# SmartMDC03.net
KiCad netlist of a schematic drawn in EAGLE
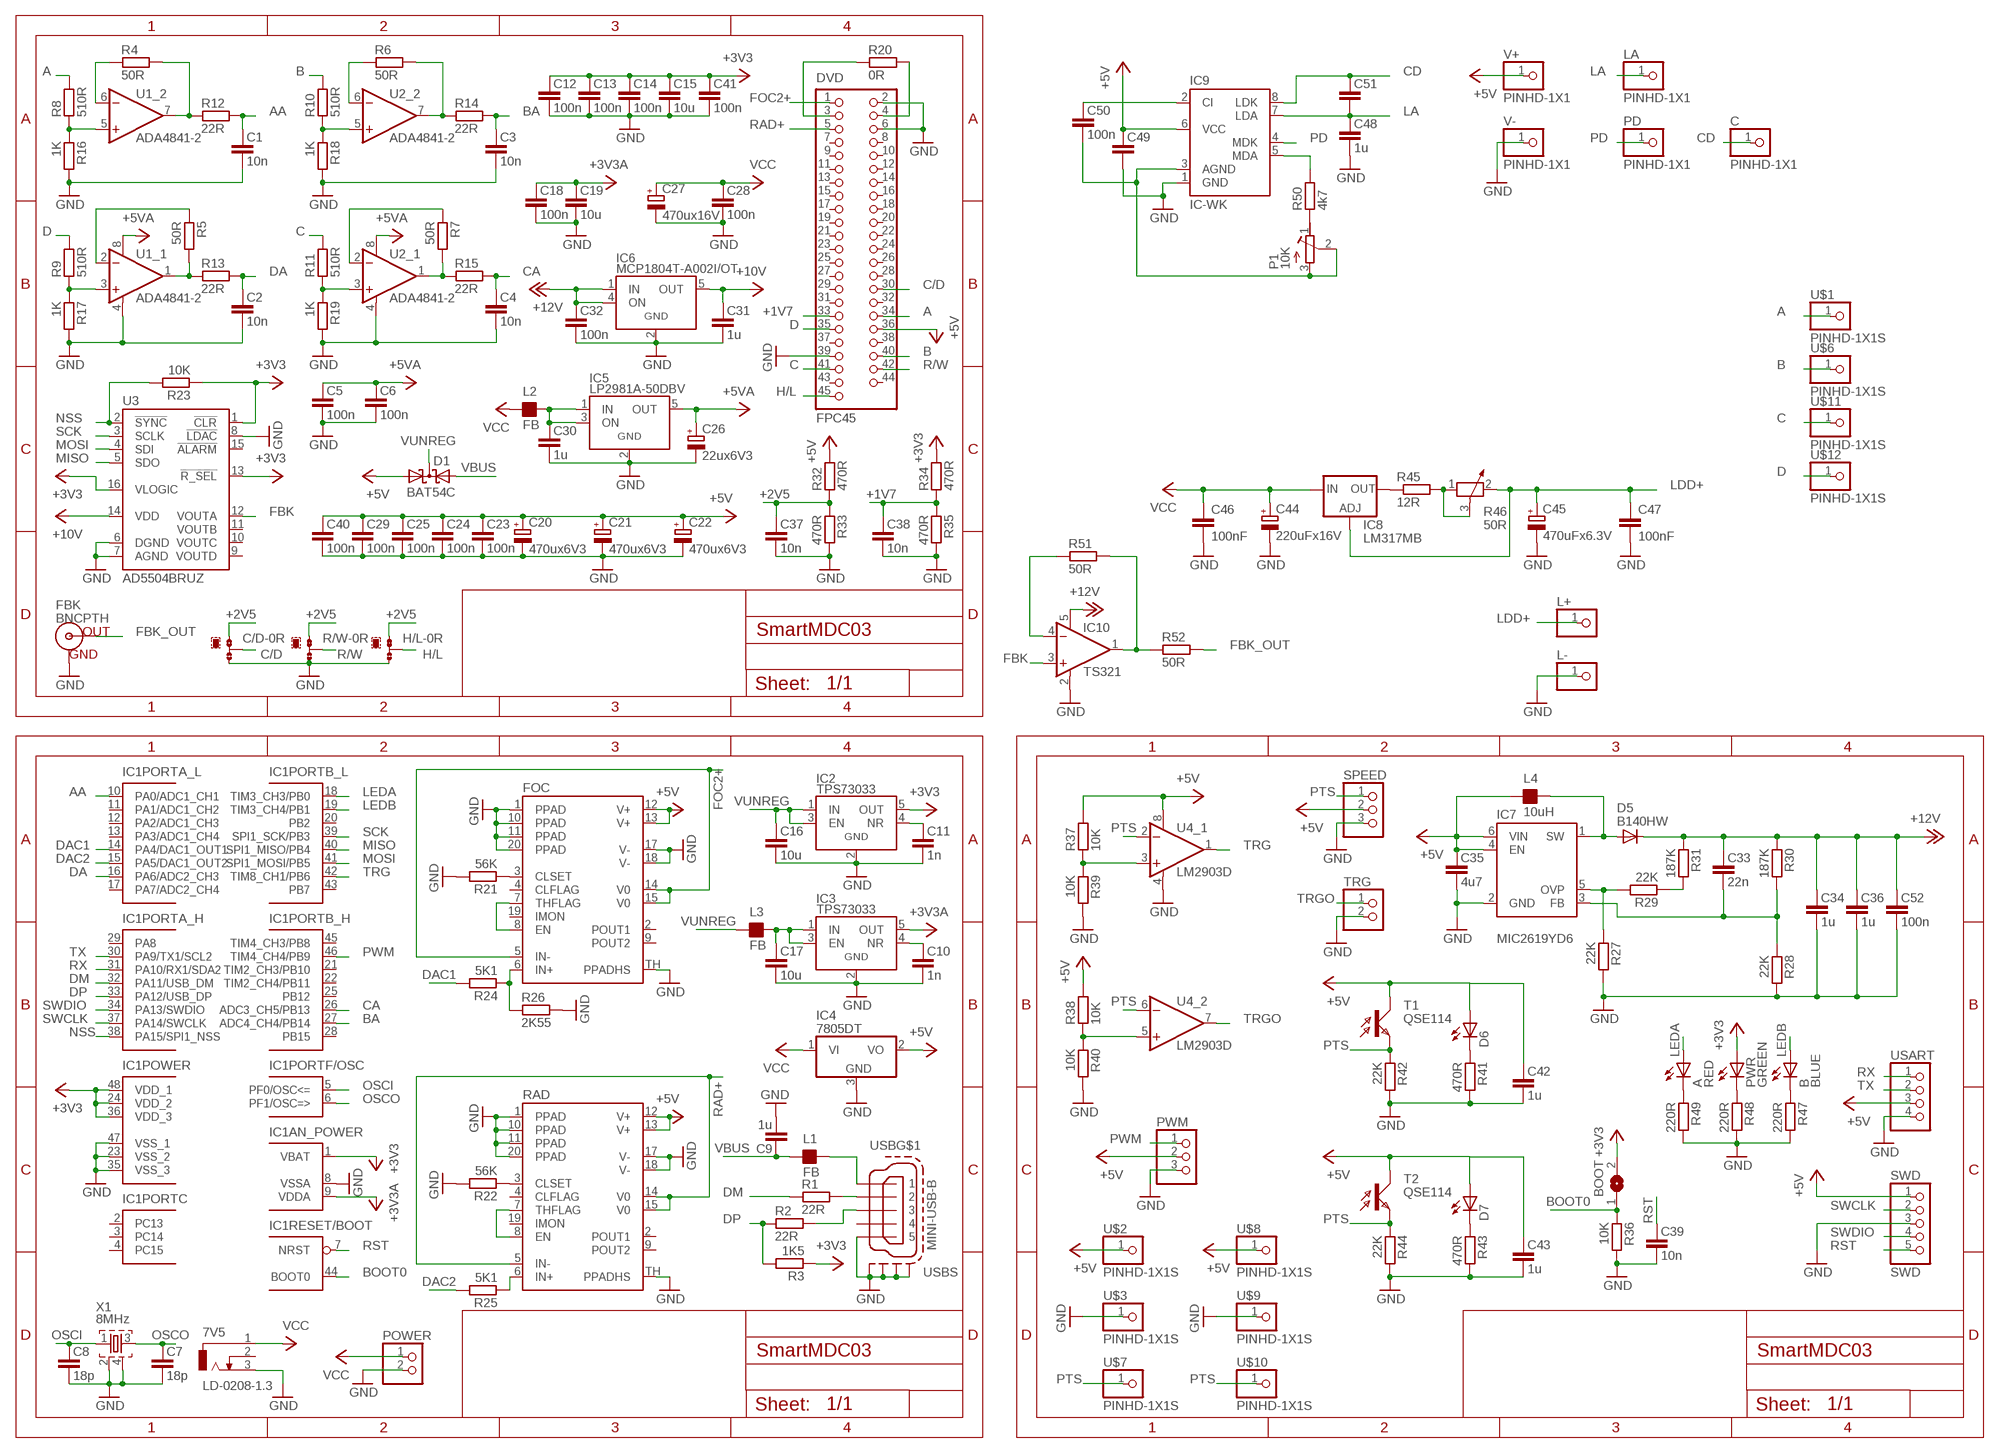
[diagram p0: schematic, sheet 1]

(export (version "E")
  (design (tool "Eeschema 10.0.6"))
  (components
    (comp (ref "7V5")
      (value "LD-0208-1.3")
      (footprint "eagle-import:LD-0208")
      (libsource (lib "eagle-import") (part "LD-0208-1.3"))
    )
    (comp (ref "A")
      (value "RED")
      (footprint "eagle-import:CHIPLED_0805")
      (libsource (lib "eagle-import") (part "LEDCHIPLED_0805"))
    )
    (comp (ref "B")
      (value "BLUE")
      (footprint "eagle-import:CHIPLED_0805")
      (libsource (lib "eagle-import") (part "LEDCHIPLED_0805"))
    )
    (comp (ref "BOOT")
      (value "SJ")
      (footprint "eagle-import:SJ")
      (libsource (lib "eagle-import") (part "SJ"))
    )
    (comp (ref "C")
      (value "PINHD-1X1")
      (footprint "eagle-import:1X01")
      (libsource (lib "eagle-import") (part "PINHD-1X1"))
    )
    (comp (ref "C/D")
      (value "0R-JUMPA")
      (footprint "eagle-import:A0R-JMP")
      (libsource (lib "eagle-import") (part "0R-JUMPA"))
    )
    (comp (ref "C1")
      (value "10n")
      (footprint "eagle-import:C0603G")
      (libsource (lib "eagle-import") (part "C_EU_C0603G"))
    )
    (comp (ref "C2")
      (value "10n")
      (footprint "eagle-import:C0603G")
      (libsource (lib "eagle-import") (part "C_EU_C0603G"))
    )
    (comp (ref "C3")
      (value "10n")
      (footprint "eagle-import:C0603G")
      (libsource (lib "eagle-import") (part "C_EU_C0603G"))
    )
    (comp (ref "C4")
      (value "10n")
      (footprint "eagle-import:C0603G")
      (libsource (lib "eagle-import") (part "C_EU_C0603G"))
    )
    (comp (ref "C5")
      (value "100n")
      (footprint "eagle-import:C0603G")
      (libsource (lib "eagle-import") (part "C_EU_C0603G"))
    )
    (comp (ref "C6")
      (value "100n")
      (footprint "eagle-import:C0603G")
      (libsource (lib "eagle-import") (part "C_EU_C0603G"))
    )
    (comp (ref "C7")
      (value "18p")
      (footprint "eagle-import:C0603G")
      (libsource (lib "eagle-import") (part "C_EU_C0603G"))
    )
    (comp (ref "C8")
      (value "18p")
      (footprint "eagle-import:C0603G")
      (libsource (lib "eagle-import") (part "C_EU_C0603G"))
    )
    (comp (ref "C9")
      (value "1u")
      (footprint "eagle-import:C0603G")
      (libsource (lib "eagle-import") (part "C_EU_C0603G"))
    )
    (comp (ref "C10")
      (value "1n")
      (footprint "eagle-import:C0603G")
      (libsource (lib "eagle-import") (part "C_EU_C0603G"))
    )
    (comp (ref "C11")
      (value "1n")
      (footprint "eagle-import:C0603G")
      (libsource (lib "eagle-import") (part "C_EU_C0603G"))
    )
    (comp (ref "C12")
      (value "100n")
      (footprint "eagle-import:C0603G")
      (libsource (lib "eagle-import") (part "C_EU_C0603G"))
    )
    (comp (ref "C13")
      (value "100n")
      (footprint "eagle-import:C0603G")
      (libsource (lib "eagle-import") (part "C_EU_C0603G"))
    )
    (comp (ref "C14")
      (value "100n")
      (footprint "eagle-import:C0603G")
      (libsource (lib "eagle-import") (part "C_EU_C0603G"))
    )
    (comp (ref "C15")
      (value "10u")
      (footprint "eagle-import:C0805G")
      (libsource (lib "eagle-import") (part "C_EU_C0805G"))
    )
    (comp (ref "C16")
      (value "10u")
      (footprint "eagle-import:C0805G")
      (libsource (lib "eagle-import") (part "C_EU_C0805G"))
    )
    (comp (ref "C17")
      (value "10u")
      (footprint "eagle-import:C0805G")
      (libsource (lib "eagle-import") (part "C_EU_C0805G"))
    )
    (comp (ref "C18")
      (value "100n")
      (footprint "eagle-import:C0603G")
      (libsource (lib "eagle-import") (part "C_EU_C0603G"))
    )
    (comp (ref "C19")
      (value "10u")
      (footprint "eagle-import:C0805G")
      (libsource (lib "eagle-import") (part "C_EU_C0805G"))
    )
    (comp (ref "C20")
      (value "470ux6V3")
      (footprint "eagle-import:SMC_D")
      (libsource (lib "eagle-import") (part "CPOL-EUSMCD"))
    )
    (comp (ref "C21")
      (value "470ux6V3")
      (footprint "eagle-import:SMC_D")
      (libsource (lib "eagle-import") (part "CPOL-EUSMCD"))
    )
    (comp (ref "C22")
      (value "470ux6V3")
      (footprint "eagle-import:SMC_D")
      (libsource (lib "eagle-import") (part "CPOL-EUSMCD"))
    )
    (comp (ref "C23")
      (value "100n")
      (footprint "eagle-import:C0603G")
      (libsource (lib "eagle-import") (part "C_EU_C0603G"))
    )
    (comp (ref "C24")
      (value "100n")
      (footprint "eagle-import:C0603G")
      (libsource (lib "eagle-import") (part "C_EU_C0603G"))
    )
    (comp (ref "C25")
      (value "100n")
      (footprint "eagle-import:C0603G")
      (libsource (lib "eagle-import") (part "C_EU_C0603G"))
    )
    (comp (ref "C26")
      (value "22ux6V3")
      (footprint "eagle-import:SMC_A")
      (libsource (lib "eagle-import") (part "CPOL-EUSMCA"))
    )
    (comp (ref "C27")
      (value "470ux16V")
      (footprint "eagle-import:E2,5-7")
      (libsource (lib "eagle-import") (part "CPOL-EUE2.5-7"))
    )
    (comp (ref "C28")
      (value "100n")
      (footprint "eagle-import:C0603G")
      (libsource (lib "eagle-import") (part "C_EU_C0603G"))
    )
    (comp (ref "C29")
      (value "100n")
      (footprint "eagle-import:C0603G")
      (libsource (lib "eagle-import") (part "C_EU_C0603G"))
    )
    (comp (ref "C30")
      (value "1u")
      (footprint "eagle-import:C0603G")
      (libsource (lib "eagle-import") (part "C_EU_C0603G"))
    )
    (comp (ref "C31")
      (value "1u")
      (footprint "eagle-import:C0603G")
      (libsource (lib "eagle-import") (part "C_EU_C0603G"))
    )
    (comp (ref "C32")
      (value "100n")
      (footprint "eagle-import:C0603G")
      (libsource (lib "eagle-import") (part "C_EU_C0603G"))
    )
    (comp (ref "C33")
      (value "22n")
      (footprint "eagle-import:C0603")
      (libsource (lib "eagle-import") (part "C_EU_C0603"))
    )
    (comp (ref "C34")
      (value "1u")
      (footprint "eagle-import:C0603G")
      (libsource (lib "eagle-import") (part "C_EU_C0603G"))
    )
    (comp (ref "C35")
      (value "4u7")
      (footprint "eagle-import:C0603G")
      (libsource (lib "eagle-import") (part "C_EU_C0603G"))
    )
    (comp (ref "C36")
      (value "1u")
      (footprint "eagle-import:C0603G")
      (libsource (lib "eagle-import") (part "C_EU_C0603G"))
    )
    (comp (ref "C37")
      (value "10n")
      (footprint "eagle-import:C0603G")
      (libsource (lib "eagle-import") (part "C_EU_C0603G"))
    )
    (comp (ref "C38")
      (value "10n")
      (footprint "eagle-import:C0603G")
      (libsource (lib "eagle-import") (part "C_EU_C0603G"))
    )
    (comp (ref "C39")
      (value "10n")
      (footprint "eagle-import:C0603G")
      (libsource (lib "eagle-import") (part "C_EU_C0603G"))
    )
    (comp (ref "C40")
      (value "100n")
      (footprint "eagle-import:C0603G")
      (libsource (lib "eagle-import") (part "C_EU_C0603G"))
    )
    (comp (ref "C41")
      (value "100n")
      (footprint "eagle-import:C0603G")
      (libsource (lib "eagle-import") (part "C_EU_C0603G"))
    )
    (comp (ref "C42")
      (value "1u")
      (footprint "eagle-import:C0603G")
      (libsource (lib "eagle-import") (part "C_EU_C0603G"))
    )
    (comp (ref "C43")
      (value "1u")
      (footprint "eagle-import:C0603G")
      (libsource (lib "eagle-import") (part "C_EU_C0603G"))
    )
    (comp (ref "C44")
      (value "220uFx16V")
      (footprint "eagle-import:E3,5-8")
      (libsource (lib "eagle-import") (part "CPOL-EUE3.5-8"))
    )
    (comp (ref "C45")
      (value "470uFx6.3V")
      (footprint "eagle-import:E3,5-8")
      (libsource (lib "eagle-import") (part "CPOL-EUE3.5-8"))
    )
    (comp (ref "C46")
      (value "100nF")
      (footprint "eagle-import:C050-024X044")
      (libsource (lib "eagle-import") (part "C-EU050-024X044"))
    )
    (comp (ref "C47")
      (value "100nF")
      (footprint "eagle-import:C050-024X044")
      (libsource (lib "eagle-import") (part "C-EU050-024X044"))
    )
    (comp (ref "C48")
      (value "1u")
      (footprint "eagle-import:C0805")
      (libsource (lib "eagle-import") (part "C_EU_C0805"))
    )
    (comp (ref "C49")
      (value "C_EU_C0805")
      (footprint "eagle-import:C0805")
      (libsource (lib "eagle-import") (part "C_EU_C0805"))
    )
    (comp (ref "C50")
      (value "100n")
      (footprint "eagle-import:C0805")
      (libsource (lib "eagle-import") (part "C_EU_C0805"))
    )
    (comp (ref "C51")
      (value "C_EU_C0805")
      (footprint "eagle-import:C0805")
      (libsource (lib "eagle-import") (part "C_EU_C0805"))
    )
    (comp (ref "C52")
      (value "100n")
      (footprint "eagle-import:C0603G")
      (libsource (lib "eagle-import") (part "C_EU_C0603G"))
    )
    (comp (ref "D1")
      (value "BAT54C")
      (footprint "eagle-import:SOT23")
      (libsource (lib "eagle-import") (part "BAT54C"))
    )
    (comp (ref "D5")
      (value "B140HW")
      (footprint "eagle-import:SOD123")
      (libsource (lib "eagle-import") (part "B140HW"))
    )
    (comp (ref "D6")
      (value "OP240")
      (footprint "eagle-import:OP240")
      (libsource (lib "eagle-import") (part "OP240"))
    )
    (comp (ref "D7")
      (value "OP240")
      (footprint "eagle-import:OP240")
      (libsource (lib "eagle-import") (part "OP240"))
    )
    (comp (ref "DVD")
      (value "FPC45")
      (footprint "eagle-import:FPC45")
      (libsource (lib "eagle-import") (part "CON-FPC45"))
    )
    (comp (ref "FBK")
      (value "BNCPTH")
      (footprint "eagle-import:BNC")
      (libsource (lib "eagle-import") (part "BNCPTH"))
    )
    (comp (ref "FOC")
      (value "OPA569")
      (footprint "eagle-import:SO-20")
      (libsource (lib "eagle-import") (part "OPA569"))
    )
    (comp (ref "H/L")
      (value "0R-JUMPA")
      (footprint "eagle-import:A0R-JMP")
      (libsource (lib "eagle-import") (part "0R-JUMPA"))
    )
    (comp (ref "IC1")
      (value "STM32F303CXT6")
      (footprint "eagle-import:LQFP48")
      (libsource (lib "eagle-import") (part "STM32F303CXT6"))
    )
    (comp (ref "IC2")
      (value "TPS73033")
      (footprint "eagle-import:SOT23-5")
      (libsource (lib "eagle-import") (part "TPS769XX"))
    )
    (comp (ref "IC3")
      (value "TPS73033")
      (footprint "eagle-import:SOT23-5")
      (libsource (lib "eagle-import") (part "TPS769XX"))
    )
    (comp (ref "IC4")
      (value "7805DT")
      (footprint "eagle-import:TO252")
      (libsource (lib "eagle-import") (part "78DT05"))
    )
    (comp (ref "IC5")
      (value "LP2981A-50DBV")
      (footprint "eagle-import:SOT23-5")
      (libsource (lib "eagle-import") (part "LP2981A-50DBV"))
    )
    (comp (ref "IC6")
      (value "MCP1804T-A002I/OT")
      (footprint "eagle-import:SOT23-5")
      (libsource (lib "eagle-import") (part "MCP1804T-A002I/OT"))
    )
    (comp (ref "IC7")
      (value "MIC2619YD6")
      (footprint "eagle-import:SOT23-6")
      (libsource (lib "eagle-import") (part "MIC2619YD6"))
    )
    (comp (ref "IC8")
      (value "LM317MB")
      (footprint "eagle-import:TO220L1")
      (libsource (lib "eagle-import") (part "LM317?MB"))
    )
    (comp (ref "IC9")
      (value "IC-WK")
      (footprint "eagle-import:SOIC-8")
      (libsource (lib "eagle-import") (part "IC-WK"))
    )
    (comp (ref "IC10")
      (value "TS321")
      (footprint "eagle-import:SOT23-5")
      (libsource (lib "eagle-import") (part "TS321"))
    )
    (comp (ref "L+")
      (value "PINHD-1X1")
      (footprint "eagle-import:1X01")
      (libsource (lib "eagle-import") (part "pinhead_PINHD-1X1"))
    )
    (comp (ref "L-")
      (value "PINHD-1X1")
      (footprint "eagle-import:1X01")
      (libsource (lib "eagle-import") (part "pinhead_PINHD-1X1"))
    )
    (comp (ref "L1")
      (value "FB")
      (footprint "eagle-import:L0603")
      (libsource (lib "eagle-import") (part "FB_0603"))
    )
    (comp (ref "L2")
      (value "FB")
      (footprint "eagle-import:L0603")
      (libsource (lib "eagle-import") (part "FB_0603"))
    )
    (comp (ref "L3")
      (value "FB")
      (footprint "eagle-import:L0603")
      (libsource (lib "eagle-import") (part "FB_0603"))
    )
    (comp (ref "L4")
      (value "10uH")
      (footprint "eagle-import:L1210")
      (libsource (lib "eagle-import") (part "FB_1210"))
    )
    (comp (ref "LA")
      (value "PINHD-1X1")
      (footprint "eagle-import:1X01")
      (libsource (lib "eagle-import") (part "PINHD-1X1"))
    )
    (comp (ref "P1")
      (value "10K")
      (footprint "eagle-import:RTRIM3165W")
      (libsource (lib "eagle-import") (part "R-TRIMM3165W"))
    )
    (comp (ref "PD")
      (value "PINHD-1X1")
      (footprint "eagle-import:1X01")
      (libsource (lib "eagle-import") (part "PINHD-1X1"))
    )
    (comp (ref "POWER")
      (value "PINHD-1X2")
      (footprint "eagle-import:1X02")
      (libsource (lib "eagle-import") (part "PINHD-1X2"))
    )
    (comp (ref "PWM")
      (value "PINHD-1X3")
      (footprint "eagle-import:1X03")
      (libsource (lib "eagle-import") (part "PINHD-1X3"))
    )
    (comp (ref "PWR")
      (value "GREEN")
      (footprint "eagle-import:CHIPLED_0805")
      (libsource (lib "eagle-import") (part "LEDCHIPLED_0805"))
    )
    (comp (ref "R/W")
      (value "0R-JUMPA")
      (footprint "eagle-import:A0R-JMP")
      (libsource (lib "eagle-import") (part "0R-JUMPA"))
    )
    (comp (ref "R1")
      (value "22R")
      (footprint "eagle-import:R0603")
      (libsource (lib "eagle-import") (part "R_EU_R0603"))
    )
    (comp (ref "R2")
      (value "22R")
      (footprint "eagle-import:R0603")
      (libsource (lib "eagle-import") (part "R_EU_R0603"))
    )
    (comp (ref "R3")
      (value "1K5")
      (footprint "eagle-import:R0603")
      (libsource (lib "eagle-import") (part "R_EU_R0603"))
    )
    (comp (ref "R4")
      (value "50R")
      (footprint "eagle-import:R0603")
      (libsource (lib "eagle-import") (part "R_EU_R0603"))
    )
    (comp (ref "R5")
      (value "50R")
      (footprint "eagle-import:R0603")
      (libsource (lib "eagle-import") (part "R_EU_R0603"))
    )
    (comp (ref "R6")
      (value "50R")
      (footprint "eagle-import:R0603")
      (libsource (lib "eagle-import") (part "R_EU_R0603"))
    )
    (comp (ref "R7")
      (value "50R")
      (footprint "eagle-import:R0603")
      (libsource (lib "eagle-import") (part "R_EU_R0603"))
    )
    (comp (ref "R8")
      (value "510R")
      (footprint "eagle-import:R0603")
      (libsource (lib "eagle-import") (part "R_EU_R0603"))
    )
    (comp (ref "R9")
      (value "510R")
      (footprint "eagle-import:R0603")
      (libsource (lib "eagle-import") (part "R_EU_R0603"))
    )
    (comp (ref "R10")
      (value "510R")
      (footprint "eagle-import:R0603")
      (libsource (lib "eagle-import") (part "R_EU_R0603"))
    )
    (comp (ref "R11")
      (value "510R")
      (footprint "eagle-import:R0603")
      (libsource (lib "eagle-import") (part "R_EU_R0603"))
    )
    (comp (ref "R12")
      (value "22R")
      (footprint "eagle-import:R0603")
      (libsource (lib "eagle-import") (part "R_EU_R0603"))
    )
    (comp (ref "R13")
      (value "22R")
      (footprint "eagle-import:R0603")
      (libsource (lib "eagle-import") (part "R_EU_R0603"))
    )
    (comp (ref "R14")
      (value "22R")
      (footprint "eagle-import:R0603")
      (libsource (lib "eagle-import") (part "R_EU_R0603"))
    )
    (comp (ref "R15")
      (value "22R")
      (footprint "eagle-import:R0603")
      (libsource (lib "eagle-import") (part "R_EU_R0603"))
    )
    (comp (ref "R16")
      (value "1K")
      (footprint "eagle-import:R0603G")
      (libsource (lib "eagle-import") (part "R_EU_R0603G"))
    )
    (comp (ref "R17")
      (value "1K")
      (footprint "eagle-import:R0603G")
      (libsource (lib "eagle-import") (part "R_EU_R0603G"))
    )
    (comp (ref "R18")
      (value "1K")
      (footprint "eagle-import:R0603G")
      (libsource (lib "eagle-import") (part "R_EU_R0603G"))
    )
    (comp (ref "R19")
      (value "1K")
      (footprint "eagle-import:R0603G")
      (libsource (lib "eagle-import") (part "R_EU_R0603G"))
    )
    (comp (ref "R20")
      (value "0R")
      (footprint "eagle-import:R0603")
      (libsource (lib "eagle-import") (part "R_EU_R0603"))
    )
    (comp (ref "R21")
      (value "56K")
      (footprint "eagle-import:R0603G")
      (libsource (lib "eagle-import") (part "R_EU_R0603G"))
    )
    (comp (ref "R22")
      (value "56K")
      (footprint "eagle-import:R0603G")
      (libsource (lib "eagle-import") (part "R_EU_R0603G"))
    )
    (comp (ref "R23")
      (value "10K")
      (footprint "eagle-import:R0603")
      (libsource (lib "eagle-import") (part "R_EU_R0603"))
    )
    (comp (ref "R24")
      (value "5K1")
      (footprint "eagle-import:R0603")
      (libsource (lib "eagle-import") (part "R_EU_R0603"))
    )
    (comp (ref "R25")
      (value "5K1")
      (footprint "eagle-import:R0603")
      (libsource (lib "eagle-import") (part "R_EU_R0603"))
    )
    (comp (ref "R26")
      (value "2K55")
      (footprint "eagle-import:R0603G")
      (libsource (lib "eagle-import") (part "R_EU_R0603G"))
    )
    (comp (ref "R27")
      (value "22K")
      (footprint "eagle-import:R0603G")
      (libsource (lib "eagle-import") (part "R_EU_R0603G"))
    )
    (comp (ref "R28")
      (value "22K")
      (footprint "eagle-import:R0603G")
      (libsource (lib "eagle-import") (part "R_EU_R0603G"))
    )
    (comp (ref "R29")
      (value "22K")
      (footprint "eagle-import:R0603")
      (libsource (lib "eagle-import") (part "R_EU_R0603"))
    )
    (comp (ref "R30")
      (value "187K")
      (footprint "eagle-import:R0603")
      (libsource (lib "eagle-import") (part "R_EU_R0603"))
    )
    (comp (ref "R31")
      (value "187K")
      (footprint "eagle-import:R0603")
      (libsource (lib "eagle-import") (part "R_EU_R0603"))
    )
    (comp (ref "R32")
      (value "470R")
      (footprint "eagle-import:R0603")
      (libsource (lib "eagle-import") (part "R_EU_R0603"))
    )
    (comp (ref "R33")
      (value "470R")
      (footprint "eagle-import:R0603G")
      (libsource (lib "eagle-import") (part "R_EU_R0603G"))
    )
    (comp (ref "R34")
      (value "470R")
      (footprint "eagle-import:R0603")
      (libsource (lib "eagle-import") (part "R_EU_R0603"))
    )
    (comp (ref "R35")
      (value "470R")
      (footprint "eagle-import:R0603G")
      (libsource (lib "eagle-import") (part "R_EU_R0603G"))
    )
    (comp (ref "R36")
      (value "10K")
      (footprint "eagle-import:R0603G")
      (libsource (lib "eagle-import") (part "R_EU_R0603G"))
    )
    (comp (ref "R37")
      (value "10K")
      (footprint "eagle-import:R0603")
      (libsource (lib "eagle-import") (part "R_EU_R0603"))
    )
    (comp (ref "R38")
      (value "10K")
      (footprint "eagle-import:R0603")
      (libsource (lib "eagle-import") (part "R_EU_R0603"))
    )
    (comp (ref "R39")
      (value "10K")
      (footprint "eagle-import:R0603G")
      (libsource (lib "eagle-import") (part "R_EU_R0603G"))
    )
    (comp (ref "R40")
      (value "10K")
      (footprint "eagle-import:R0603G")
      (libsource (lib "eagle-import") (part "R_EU_R0603G"))
    )
    (comp (ref "R41")
      (value "470R")
      (footprint "eagle-import:R0603G")
      (libsource (lib "eagle-import") (part "R_EU_R0603G"))
    )
    (comp (ref "R42")
      (value "22K")
      (footprint "eagle-import:R0603G")
      (libsource (lib "eagle-import") (part "R_EU_R0603G"))
    )
    (comp (ref "R43")
      (value "470R")
      (footprint "eagle-import:R0603G")
      (libsource (lib "eagle-import") (part "R_EU_R0603G"))
    )
    (comp (ref "R44")
      (value "22K")
      (footprint "eagle-import:R0603G")
      (libsource (lib "eagle-import") (part "R_EU_R0603G"))
    )
    (comp (ref "R45")
      (value "12R")
      (footprint "eagle-import:0207_7")
      (libsource (lib "eagle-import") (part "R-EU_0207/7"))
    )
    (comp (ref "R46")
      (value "50R")
      (footprint "eagle-import:PT-SPIN")
      (libsource (lib "eagle-import") (part "POTENTIOMETER_PT_SPIN"))
    )
    (comp (ref "R47")
      (value "220R")
      (footprint "eagle-import:R0603G")
      (libsource (lib "eagle-import") (part "R_EU_R0603G"))
    )
    (comp (ref "R48")
      (value "220R")
      (footprint "eagle-import:R0603G")
      (libsource (lib "eagle-import") (part "R_EU_R0603G"))
    )
    (comp (ref "R49")
      (value "220R")
      (footprint "eagle-import:R0603G")
      (libsource (lib "eagle-import") (part "R_EU_R0603G"))
    )
    (comp (ref "R50")
      (value "4k7")
      (footprint "eagle-import:R0805")
      (libsource (lib "eagle-import") (part "R_EU_R0805"))
    )
    (comp (ref "R51")
      (value "50R")
      (footprint "eagle-import:R0603")
      (libsource (lib "eagle-import") (part "R_EU_R0603"))
    )
    (comp (ref "R52")
      (value "50R")
      (footprint "eagle-import:R0603")
      (libsource (lib "eagle-import") (part "R_EU_R0603"))
    )
    (comp (ref "RAD")
      (value "OPA569")
      (footprint "eagle-import:SO-20")
      (libsource (lib "eagle-import") (part "OPA569"))
    )
    (comp (ref "SPEED")
      (value "PINHD-1X3")
      (footprint "eagle-import:1X03")
      (libsource (lib "eagle-import") (part "PINHD-1X3"))
    )
    (comp (ref "SWD")
      (value "SWD")
      (footprint "eagle-import:1X05")
      (libsource (lib "eagle-import") (part "PINHD-1X5"))
    )
    (comp (ref "T1")
      (value "QSE114")
      (footprint "eagle-import:QSE114")
      (libsource (lib "eagle-import") (part "QSE114"))
    )
    (comp (ref "T2")
      (value "QSE114")
      (footprint "eagle-import:QSE114")
      (libsource (lib "eagle-import") (part "QSE114"))
    )
    (comp (ref "TRG")
      (value "PINHD-1X2")
      (footprint "eagle-import:1X02")
      (libsource (lib "eagle-import") (part "PINHD-1X2"))
    )
    (comp (ref "U$1")
      (value "PINHD-1X1S")
      (footprint "eagle-import:1X01S")
      (libsource (lib "eagle-import") (part "PINHD-1X1S"))
    )
    (comp (ref "U$2")
      (value "PINHD-1X1S")
      (footprint "eagle-import:1X01S")
      (libsource (lib "eagle-import") (part "PINHD-1X1S"))
    )
    (comp (ref "U$3")
      (value "PINHD-1X1S")
      (footprint "eagle-import:1X01S")
      (libsource (lib "eagle-import") (part "PINHD-1X1S"))
    )
    (comp (ref "U$6")
      (value "PINHD-1X1S")
      (footprint "eagle-import:1X01S")
      (libsource (lib "eagle-import") (part "PINHD-1X1S"))
    )
    (comp (ref "U$7")
      (value "PINHD-1X1S")
      (footprint "eagle-import:1X01S")
      (libsource (lib "eagle-import") (part "PINHD-1X1S"))
    )
    (comp (ref "U$8")
      (value "PINHD-1X1S")
      (footprint "eagle-import:1X01S")
      (libsource (lib "eagle-import") (part "PINHD-1X1S"))
    )
    (comp (ref "U$9")
      (value "PINHD-1X1S")
      (footprint "eagle-import:1X01S")
      (libsource (lib "eagle-import") (part "PINHD-1X1S"))
    )
    (comp (ref "U$10")
      (value "PINHD-1X1S")
      (footprint "eagle-import:1X01S")
      (libsource (lib "eagle-import") (part "PINHD-1X1S"))
    )
    (comp (ref "U$11")
      (value "PINHD-1X1S")
      (footprint "eagle-import:1X01S")
      (libsource (lib "eagle-import") (part "PINHD-1X1S"))
    )
    (comp (ref "U$12")
      (value "PINHD-1X1S")
      (footprint "eagle-import:1X01S")
      (libsource (lib "eagle-import") (part "PINHD-1X1S"))
    )
    (comp (ref "U1")
      (value "ADA4841-2")
      (footprint "eagle-import:SOIC-8")
      (libsource (lib "eagle-import") (part "ADA4841-2"))
    )
    (comp (ref "U2")
      (value "ADA4841-2")
      (footprint "eagle-import:SOIC-8")
      (libsource (lib "eagle-import") (part "ADA4841-2"))
    )
    (comp (ref "U3")
      (value "AD5504BRUZ")
      (footprint "eagle-import:TSSOP16")
      (libsource (lib "eagle-import") (part "AD5504BRUZ"))
    )
    (comp (ref "U4")
      (value "LM2903D")
      (footprint "eagle-import:SOIC-8")
      (libsource (lib "eagle-import") (part "LM2903D"))
    )
    (comp (ref "USART")
      (value "PINHD-1X4")
      (footprint "eagle-import:1X04")
      (libsource (lib "eagle-import") (part "PINHD-1X4"))
    )
    (comp (ref "USB")
      (value "MINI-USB-B")
      (footprint "eagle-import:32005-201")
      (libsource (lib "eagle-import") (part "MINI-USB-SCHIELD-32005-201"))
    )
    (comp (ref "V+")
      (value "PINHD-1X1")
      (footprint "eagle-import:1X01")
      (libsource (lib "eagle-import") (part "PINHD-1X1"))
    )
    (comp (ref "V-")
      (value "PINHD-1X1")
      (footprint "eagle-import:1X01")
      (libsource (lib "eagle-import") (part "PINHD-1X1"))
    )
    (comp (ref "X1")
      (value "8MHz")
      (footprint "eagle-import:ABMM2")
      (libsource (lib "eagle-import") (part "ABMM2"))
    )
  )
  (nets
    (net (code "1") (name "+3V3") (class "Default")
      (node (ref "BOOT") (pin "2") (pinfunction "2_2") (pintype "passive"))
      (node (ref "C12") (pin "1") (pinfunction "1_1") (pintype "passive"))
      (node (ref "C13") (pin "1") (pinfunction "1_1") (pintype "passive"))
      (node (ref "C14") (pin "1") (pinfunction "1_1") (pintype "passive"))
      (node (ref "C15") (pin "1") (pinfunction "1_1") (pintype "passive"))
      (node (ref "C41") (pin "1") (pinfunction "1_1") (pintype "passive"))
      (node (ref "IC1") (pin "1") (pinfunction "VBAT_1") (pintype "power_in"))
      (node (ref "IC1") (pin "24") (pinfunction "VDD_2_24") (pintype "power_in"))
      (node (ref "IC1") (pin "36") (pinfunction "VDD_3_36") (pintype "power_in"))
      (node (ref "IC1") (pin "48") (pinfunction "VDD_1_48") (pintype "power_in"))
      (node (ref "IC2") (pin "5") (pinfunction "OUT_5") (pintype "power_in"))
      (node (ref "PWR") (pin "A") (pinfunction "A_A") (pintype "passive"))
      (node (ref "R23") (pin "1") (pinfunction "1_1") (pintype "passive"))
      (node (ref "R3") (pin "1") (pinfunction "1_1") (pintype "passive"))
      (node (ref "R34") (pin "2") (pinfunction "2_2") (pintype "passive"))
      (node (ref "U3") (pin "1") (pinfunction "~{CLR}_1") (pintype "input"))
      (node (ref "U3") (pin "13") (pinfunction "~{R_SEL}_13") (pintype "input"))
      (node (ref "U3") (pin "16") (pinfunction "VLOGIC_16") (pintype "power_in"))
    )
    (net (code "2") (name "+3V3A") (class "Default")
      (node (ref "C18") (pin "1") (pinfunction "1_1") (pintype "passive"))
      (node (ref "C19") (pin "1") (pinfunction "1_1") (pintype "passive"))
      (node (ref "IC1") (pin "9") (pinfunction "VDDA_9") (pintype "power_in"))
      (node (ref "IC3") (pin "5") (pinfunction "OUT_5") (pintype "power_in"))
    )
    (net (code "3") (name "+5V") (class "Default")
      (node (ref "C20") (pin "+") (pinfunction "+_+") (pintype "passive"))
      (node (ref "C21") (pin "+") (pinfunction "+_+") (pintype "passive"))
      (node (ref "C22") (pin "+") (pinfunction "+_+") (pintype "passive"))
      (node (ref "C23") (pin "1") (pinfunction "1_1") (pintype "passive"))
      (node (ref "C24") (pin "1") (pinfunction "1_1") (pintype "passive"))
      (node (ref "C25") (pin "1") (pinfunction "1_1") (pintype "passive"))
      (node (ref "C29") (pin "1") (pinfunction "1_1") (pintype "passive"))
      (node (ref "C35") (pin "1") (pinfunction "1_1") (pintype "passive"))
      (node (ref "C40") (pin "1") (pinfunction "1_1") (pintype "passive"))
      (node (ref "C42") (pin "1") (pinfunction "1_1") (pintype "passive"))
      (node (ref "C43") (pin "1") (pinfunction "1_1") (pintype "passive"))
      (node (ref "C49") (pin "1") (pinfunction "1_1") (pintype "passive"))
      (node (ref "D1") (pin "1") (pinfunction "A1_1") (pintype "passive"))
      (node (ref "D6") (pin "A") (pinfunction "A_A") (pintype "passive"))
      (node (ref "D7") (pin "A") (pinfunction "A_A") (pintype "passive"))
      (node (ref "DVD") (pin "36") (pinfunction "36_36") (pintype "passive"))
      (node (ref "FOC") (pin "12") (pinfunction "V+_12") (pintype "bidirectional"))
      (node (ref "FOC") (pin "13") (pinfunction "V+_13") (pintype "bidirectional"))
      (node (ref "IC4") (pin "2") (pinfunction "VO_2") (pintype "passive"))
      (node (ref "IC7") (pin "4") (pinfunction "EN_4") (pintype "input"))
      (node (ref "IC7") (pin "6") (pinfunction "VIN_6") (pintype "power_in"))
      (node (ref "IC9") (pin "6") (pinfunction "VCC_6") (pintype "bidirectional"))
      (node (ref "L4") (pin "1") (pinfunction "1_1") (pintype "passive"))
      (node (ref "PWM") (pin "2") (pinfunction "2_2") (pintype "passive"))
      (node (ref "R32") (pin "2") (pinfunction "2_2") (pintype "passive"))
      (node (ref "R37") (pin "2") (pinfunction "2_2") (pintype "passive"))
      (node (ref "R38") (pin "2") (pinfunction "2_2") (pintype "passive"))
      (node (ref "RAD") (pin "12") (pinfunction "V+_12") (pintype "bidirectional"))
      (node (ref "RAD") (pin "13") (pinfunction "V+_13") (pintype "bidirectional"))
      (node (ref "SPEED") (pin "2") (pinfunction "2_2") (pintype "passive"))
      (node (ref "SWD") (pin "1") (pinfunction "1_1") (pintype "passive"))
      (node (ref "T1") (pin "C") (pinfunction "C_C") (pintype "passive"))
      (node (ref "T2") (pin "C") (pinfunction "C_C") (pintype "passive"))
      (node (ref "U$2") (pin "1") (pinfunction "1_1") (pintype "passive"))
      (node (ref "U$8") (pin "1") (pinfunction "1_1") (pintype "passive"))
      (node (ref "U4") (pin "8") (pinfunction "V+_8") (pintype "power_in"))
      (node (ref "USART") (pin "3") (pinfunction "3_3") (pintype "passive"))
      (node (ref "V+") (pin "1") (pinfunction "1_1") (pintype "passive"))
    )
    (net (code "4") (name "+5VA") (class "Default")
      (node (ref "C26") (pin "+") (pinfunction "+_+") (pintype "passive"))
      (node (ref "C5") (pin "1") (pinfunction "1_1") (pintype "passive"))
      (node (ref "C6") (pin "1") (pinfunction "1_1") (pintype "passive"))
      (node (ref "IC5") (pin "5") (pinfunction "OUT_5") (pintype "power_in"))
      (node (ref "U1") (pin "8") (pinfunction "V+_8") (pintype "power_in"))
      (node (ref "U2") (pin "8") (pinfunction "V+_8") (pintype "power_in"))
    )
    (net (code "5") (name "+10V") (class "Default")
      (node (ref "C31") (pin "1") (pinfunction "1_1") (pintype "passive"))
      (node (ref "IC6") (pin "5") (pinfunction "OUT_5") (pintype "power_in"))
      (node (ref "U3") (pin "14") (pinfunction "VDD_14") (pintype "power_in"))
    )
    (net (code "6") (name "+12V") (class "Default")
      (node (ref "C32") (pin "1") (pinfunction "1_1") (pintype "passive"))
      (node (ref "C33") (pin "1") (pinfunction "1_1") (pintype "passive"))
      (node (ref "C34") (pin "1") (pinfunction "1_1") (pintype "passive"))
      (node (ref "C36") (pin "1") (pinfunction "1_1") (pintype "passive"))
      (node (ref "C52") (pin "1") (pinfunction "1_1") (pintype "passive"))
      (node (ref "D5") (pin "C") (pinfunction "C_C") (pintype "passive"))
      (node (ref "IC10") (pin "5") (pinfunction "V+_5") (pintype "power_in"))
      (node (ref "IC6") (pin "1") (pinfunction "IN_1") (pintype "power_in"))
      (node (ref "IC6") (pin "4") (pinfunction "ON_4") (pintype "passive"))
      (node (ref "R30") (pin "1") (pinfunction "1_1") (pintype "passive"))
      (node (ref "R31") (pin "1") (pinfunction "1_1") (pintype "passive"))
    )
    (net (code "7") (name "/+1V7") (class "Default")
      (node (ref "C38") (pin "1") (pinfunction "1_1") (pintype "passive"))
      (node (ref "DVD") (pin "33") (pinfunction "33_33") (pintype "passive"))
      (node (ref "R34") (pin "1") (pinfunction "1_1") (pintype "passive"))
      (node (ref "R35") (pin "1") (pinfunction "1_1") (pintype "passive"))
    )
    (net (code "8") (name "/+2V5") (class "Default")
      (node (ref "C/D") (pin "1") (pinfunction "1_1") (pintype "passive"))
      (node (ref "C37") (pin "1") (pinfunction "1_1") (pintype "passive"))
      (node (ref "H/L") (pin "1") (pinfunction "1_1") (pintype "passive"))
      (node (ref "R/W") (pin "1") (pinfunction "1_1") (pintype "passive"))
      (node (ref "R32") (pin "1") (pinfunction "1_1") (pintype "passive"))
      (node (ref "R33") (pin "1") (pinfunction "1_1") (pintype "passive"))
    )
    (net (code "9") (name "/A") (class "Default")
      (node (ref "DVD") (pin "34") (pinfunction "34_34") (pintype "passive"))
      (node (ref "R8") (pin "2") (pinfunction "2_2") (pintype "passive"))
      (node (ref "U$1") (pin "1") (pinfunction "1_1") (pintype "passive"))
    )
    (net (code "10") (name "/AA") (class "Default")
      (node (ref "C1") (pin "1") (pinfunction "1_1") (pintype "passive"))
      (node (ref "IC1") (pin "10") (pinfunction "PA0/ADC1_CH1_10") (pintype "bidirectional"))
      (node (ref "R12") (pin "2") (pinfunction "2_2") (pintype "passive"))
    )
    (net (code "11") (name "/B") (class "Default")
      (node (ref "DVD") (pin "40") (pinfunction "40_40") (pintype "passive"))
      (node (ref "R10") (pin "2") (pinfunction "2_2") (pintype "passive"))
      (node (ref "U$6") (pin "1") (pinfunction "1_1") (pintype "passive"))
    )
    (net (code "12") (name "/BA") (class "Default")
      (node (ref "C3") (pin "1") (pinfunction "1_1") (pintype "passive"))
      (node (ref "IC1") (pin "27") (pinfunction "ADC4_CH4/PB14_27") (pintype "bidirectional"))
      (node (ref "R14") (pin "2") (pinfunction "2_2") (pintype "passive"))
    )
    (net (code "13") (name "/BOOT0") (class "Default")
      (node (ref "BOOT") (pin "1") (pinfunction "1_1") (pintype "passive"))
      (node (ref "IC1") (pin "44") (pinfunction "BOOT0_44") (pintype "input"))
      (node (ref "R36") (pin "1") (pinfunction "1_1") (pintype "passive"))
    )
    (net (code "14") (name "/C") (class "Default")
      (node (ref "DVD") (pin "41") (pinfunction "41_41") (pintype "passive"))
      (node (ref "R11") (pin "2") (pinfunction "2_2") (pintype "passive"))
      (node (ref "U$11") (pin "1") (pinfunction "1_1") (pintype "passive"))
    )
    (net (code "15") (name "/CA") (class "Default")
      (node (ref "C4") (pin "1") (pinfunction "1_1") (pintype "passive"))
      (node (ref "IC1") (pin "26") (pinfunction "ADC3_CH5/PB13_26") (pintype "bidirectional"))
      (node (ref "R15") (pin "2") (pinfunction "2_2") (pintype "passive"))
    )
    (net (code "16") (name "/CD") (class "Default")
      (node (ref "C") (pin "1") (pinfunction "1_1") (pintype "passive"))
      (node (ref "C51") (pin "1") (pinfunction "1_1") (pintype "passive"))
      (node (ref "IC9") (pin "8") (pinfunction "LDK_8") (pintype "bidirectional"))
    )
    (net (code "17") (name "/C{slash}D") (class "Default")
      (node (ref "C/D") (pin "2") (pinfunction "2_2") (pintype "passive"))
      (node (ref "DVD") (pin "30") (pinfunction "30_30") (pintype "passive"))
    )
    (net (code "18") (name "/D") (class "Default")
      (node (ref "DVD") (pin "35") (pinfunction "35_35") (pintype "passive"))
      (node (ref "R9") (pin "2") (pinfunction "2_2") (pintype "passive"))
      (node (ref "U$12") (pin "1") (pinfunction "1_1") (pintype "passive"))
    )
    (net (code "19") (name "/DA") (class "Default")
      (node (ref "C2") (pin "1") (pinfunction "1_1") (pintype "passive"))
      (node (ref "IC1") (pin "16") (pinfunction "PA6/ADC2_CH3_16") (pintype "bidirectional"))
      (node (ref "R13") (pin "2") (pinfunction "2_2") (pintype "passive"))
    )
    (net (code "20") (name "/DAC1") (class "Default")
      (node (ref "IC1") (pin "14") (pinfunction "PA4/DAC1_OUT1_14") (pintype "bidirectional"))
      (node (ref "R24") (pin "2") (pinfunction "2_2") (pintype "passive"))
    )
    (net (code "21") (name "/DAC2") (class "Default")
      (node (ref "IC1") (pin "15") (pinfunction "PA5/DAC1_OUT2_15") (pintype "bidirectional"))
      (node (ref "R25") (pin "2") (pinfunction "2_2") (pintype "passive"))
    )
    (net (code "22") (name "/DM") (class "Default")
      (node (ref "IC1") (pin "32") (pinfunction "PA11/USB_DM_32") (pintype "bidirectional"))
      (node (ref "R1") (pin "1") (pinfunction "1_1") (pintype "passive"))
    )
    (net (code "23") (name "/DP") (class "Default")
      (node (ref "IC1") (pin "33") (pinfunction "PA12/USB_DP_33") (pintype "bidirectional"))
      (node (ref "R2") (pin "1") (pinfunction "1_1") (pintype "passive"))
      (node (ref "R3") (pin "2") (pinfunction "2_2") (pintype "passive"))
    )
    (net (code "24") (name "/FBK") (class "Default")
      (node (ref "IC10") (pin "3") (pinfunction "+IN_3") (pintype "input"))
      (node (ref "U3") (pin "12") (pinfunction "VOUTA_12") (pintype "output"))
    )
    (net (code "25") (name "/FBK_OUT") (class "Default")
      (node (ref "FBK") (pin "S") (pinfunction "OUT_S") (pintype "bidirectional"))
      (node (ref "R52") (pin "2") (pinfunction "2_2") (pintype "passive"))
    )
    (net (code "26") (name "/FOC2+") (class "Default")
      (node (ref "DVD") (pin "1") (pinfunction "1_1") (pintype "passive"))
      (node (ref "FOC") (pin "14") (pinfunction "V0_14") (pintype "bidirectional"))
      (node (ref "FOC") (pin "15") (pinfunction "V0_15") (pintype "bidirectional"))
      (node (ref "FOC") (pin "5") (pinfunction "IN-_5") (pintype "bidirectional"))
    )
    (net (code "27") (name "/H{slash}L") (class "Default")
      (node (ref "DVD") (pin "45") (pinfunction "45_45") (pintype "passive"))
      (node (ref "H/L") (pin "2") (pinfunction "2_2") (pintype "passive"))
    )
    (net (code "28") (name "/LA") (class "Default")
      (node (ref "C48") (pin "1") (pinfunction "1_1") (pintype "passive"))
      (node (ref "C51") (pin "2") (pinfunction "2_2") (pintype "passive"))
      (node (ref "IC9") (pin "7") (pinfunction "LDA_7") (pintype "bidirectional"))
      (node (ref "LA") (pin "1") (pinfunction "1_1") (pintype "passive"))
    )
    (net (code "29") (name "/LDD+") (class "Default")
      (node (ref "C45") (pin "+") (pinfunction "+_+") (pintype "passive"))
      (node (ref "C47") (pin "1") (pinfunction "1_1") (pintype "passive"))
      (node (ref "IC8") (pin "1") (pinfunction "ADJ_1") (pintype "input"))
      (node (ref "L+") (pin "1") (pinfunction "1_1") (pintype "passive"))
      (node (ref "R46") (pin "2") (pinfunction "2_2") (pintype "passive"))
    )
    (net (code "30") (name "/LEDA") (class "Default")
      (node (ref "A") (pin "A") (pinfunction "A_A") (pintype "passive"))
      (node (ref "IC1") (pin "18") (pinfunction "TIM3_CH3/PB0_18") (pintype "bidirectional"))
    )
    (net (code "31") (name "/LEDB") (class "Default")
      (node (ref "B") (pin "A") (pinfunction "A_A") (pintype "passive"))
      (node (ref "IC1") (pin "19") (pinfunction "TIM3_CH4/PB1_19") (pintype "bidirectional"))
    )
    (net (code "32") (name "/MISO") (class "Default")
      (node (ref "IC1") (pin "40") (pinfunction "SPI1_MISO/PB4_40") (pintype "bidirectional"))
      (node (ref "U3") (pin "5") (pinfunction "SDO_5") (pintype "output"))
    )
    (net (code "33") (name "/MOSI") (class "Default")
      (node (ref "IC1") (pin "41") (pinfunction "SPI1_MOSI/PB5_41") (pintype "bidirectional"))
      (node (ref "U3") (pin "4") (pinfunction "SDI_4") (pintype "input"))
    )
    (net (code "34") (name "/NSS") (class "Default")
      (node (ref "IC1") (pin "38") (pinfunction "PA15/SPI1_NSS_38") (pintype "bidirectional"))
      (node (ref "R23") (pin "2") (pinfunction "2_2") (pintype "passive"))
      (node (ref "U3") (pin "2") (pinfunction "~{SYNC}_2") (pintype "input"))
    )
    (net (code "35") (name "/OSCI") (class "Default")
      (node (ref "C8") (pin "1") (pinfunction "1_1") (pintype "passive"))
      (node (ref "IC1") (pin "5") (pinfunction "PF0/OSC<=_5") (pintype "bidirectional"))
      (node (ref "X1") (pin "1") (pinfunction "1_1") (pintype "passive"))
    )
    (net (code "36") (name "/OSCO") (class "Default")
      (node (ref "C7") (pin "1") (pinfunction "1_1") (pintype "passive"))
      (node (ref "IC1") (pin "6") (pinfunction "PF1/OSC=>_6") (pintype "bidirectional"))
      (node (ref "X1") (pin "3") (pinfunction "3_3") (pintype "passive"))
    )
    (net (code "37") (name "/PD") (class "Default")
      (node (ref "IC9") (pin "4") (pinfunction "MDK_4") (pintype "bidirectional"))
      (node (ref "PD") (pin "1") (pinfunction "1_1") (pintype "passive"))
    )
    (net (code "38") (name "/PTS") (class "Default")
      (node (ref "R42") (pin "1") (pinfunction "1_1") (pintype "passive"))
      (node (ref "R44") (pin "1") (pinfunction "1_1") (pintype "passive"))
      (node (ref "SPEED") (pin "1") (pinfunction "1_1") (pintype "passive"))
      (node (ref "T1") (pin "E") (pinfunction "E_E") (pintype "passive"))
      (node (ref "T2") (pin "E") (pinfunction "E_E") (pintype "passive"))
      (node (ref "U$10") (pin "1") (pinfunction "1_1") (pintype "passive"))
      (node (ref "U$7") (pin "1") (pinfunction "1_1") (pintype "passive"))
      (node (ref "U4") (pin "2") (pinfunction "-IN_2") (pintype "input"))
      (node (ref "U4") (pin "6") (pinfunction "-IN_6") (pintype "input"))
    )
    (net (code "39") (name "/PWM") (class "Default")
      (node (ref "IC1") (pin "46") (pinfunction "TIM4_CH4/PB9_46") (pintype "bidirectional"))
      (node (ref "PWM") (pin "1") (pinfunction "1_1") (pintype "passive"))
    )
    (net (code "40") (name "/RAD+") (class "Default")
      (node (ref "DVD") (pin "5") (pinfunction "5_5") (pintype "passive"))
      (node (ref "RAD") (pin "14") (pinfunction "V0_14") (pintype "bidirectional"))
      (node (ref "RAD") (pin "15") (pinfunction "V0_15") (pintype "bidirectional"))
      (node (ref "RAD") (pin "5") (pinfunction "IN-_5") (pintype "bidirectional"))
    )
    (net (code "41") (name "/RST") (class "Default")
      (node (ref "C39") (pin "1") (pinfunction "1_1") (pintype "passive"))
      (node (ref "IC1") (pin "7") (pinfunction "NRST_7") (pintype "input"))
      (node (ref "SWD") (pin "5") (pinfunction "5_5") (pintype "passive"))
    )
    (net (code "42") (name "/RX") (class "Default")
      (node (ref "IC1") (pin "31") (pinfunction "PA10/RX1/SDA2_31") (pintype "bidirectional"))
      (node (ref "USART") (pin "1") (pinfunction "1_1") (pintype "passive"))
    )
    (net (code "43") (name "/R{slash}W") (class "Default")
      (node (ref "DVD") (pin "42") (pinfunction "42_42") (pintype "passive"))
      (node (ref "R/W") (pin "2") (pinfunction "2_2") (pintype "passive"))
    )
    (net (code "44") (name "/SCK") (class "Default")
      (node (ref "IC1") (pin "39") (pinfunction "SPI1_SCK/PB3_39") (pintype "bidirectional"))
      (node (ref "U3") (pin "3") (pinfunction "SCLK_3") (pintype "input"))
    )
    (net (code "45") (name "/SWCLK") (class "Default")
      (node (ref "IC1") (pin "37") (pinfunction "PA14/SWCLK_37") (pintype "bidirectional"))
      (node (ref "SWD") (pin "2") (pinfunction "2_2") (pintype "passive"))
    )
    (net (code "46") (name "/SWDIO") (class "Default")
      (node (ref "IC1") (pin "34") (pinfunction "PA13/SWDIO_34") (pintype "bidirectional"))
      (node (ref "SWD") (pin "4") (pinfunction "4_4") (pintype "passive"))
    )
    (net (code "47") (name "/TRG") (class "Default")
      (node (ref "IC1") (pin "42") (pinfunction "TIM8_CH1/PB6_42") (pintype "bidirectional"))
      (node (ref "U4") (pin "1") (pinfunction "OUT_1") (pintype "output"))
    )
    (net (code "48") (name "/TRGO") (class "Default")
      (node (ref "TRG") (pin "1") (pinfunction "1_1") (pintype "passive"))
      (node (ref "U4") (pin "7") (pinfunction "OUT_7") (pintype "output"))
    )
    (net (code "49") (name "/TX") (class "Default")
      (node (ref "IC1") (pin "30") (pinfunction "PA9/TX1/SCL2_30") (pintype "bidirectional"))
      (node (ref "USART") (pin "2") (pinfunction "2_2") (pintype "passive"))
    )
    (net (code "50") (name "/VBUS") (class "Default")
      (node (ref "C9") (pin "1") (pinfunction "1_1") (pintype "passive"))
      (node (ref "D1") (pin "2") (pinfunction "A2_2") (pintype "passive"))
      (node (ref "L1") (pin "1") (pinfunction "1_1") (pintype "passive"))
    )
    (net (code "51") (name "/VUNREG") (class "Default")
      (node (ref "C16") (pin "1") (pinfunction "1_1") (pintype "passive"))
      (node (ref "D1") (pin "3") (pinfunction "CC_3") (pintype "passive"))
      (node (ref "IC2") (pin "1") (pinfunction "IN_1") (pintype "power_in"))
      (node (ref "IC2") (pin "3") (pinfunction "EN_3") (pintype "passive"))
      (node (ref "L3") (pin "1") (pinfunction "1_1") (pintype "passive"))
    )
    (net (code "52") (name "GND") (class "Default")
      (node (ref "7V5") (pin "3") (pinfunction "3_3") (pintype "passive"))
      (node (ref "C/D") (pin "3") (pinfunction "3_3") (pintype "passive"))
      (node (ref "C1") (pin "2") (pinfunction "2_2") (pintype "passive"))
      (node (ref "C10") (pin "2") (pinfunction "2_2") (pintype "passive"))
      (node (ref "C11") (pin "2") (pinfunction "2_2") (pintype "passive"))
      (node (ref "C12") (pin "2") (pinfunction "2_2") (pintype "passive"))
      (node (ref "C13") (pin "2") (pinfunction "2_2") (pintype "passive"))
      (node (ref "C14") (pin "2") (pinfunction "2_2") (pintype "passive"))
      (node (ref "C15") (pin "2") (pinfunction "2_2") (pintype "passive"))
      (node (ref "C16") (pin "2") (pinfunction "2_2") (pintype "passive"))
      (node (ref "C17") (pin "2") (pinfunction "2_2") (pintype "passive"))
      (node (ref "C18") (pin "2") (pinfunction "2_2") (pintype "passive"))
      (node (ref "C19") (pin "2") (pinfunction "2_2") (pintype "passive"))
      (node (ref "C2") (pin "2") (pinfunction "2_2") (pintype "passive"))
      (node (ref "C20") (pin "-") (pinfunction "-_-") (pintype "passive"))
      (node (ref "C21") (pin "-") (pinfunction "-_-") (pintype "passive"))
      (node (ref "C22") (pin "-") (pinfunction "-_-") (pintype "passive"))
      (node (ref "C23") (pin "2") (pinfunction "2_2") (pintype "passive"))
      (node (ref "C24") (pin "2") (pinfunction "2_2") (pintype "passive"))
      (node (ref "C25") (pin "2") (pinfunction "2_2") (pintype "passive"))
      (node (ref "C26") (pin "-") (pinfunction "-_-") (pintype "passive"))
      (node (ref "C27") (pin "-") (pinfunction "-_-") (pintype "passive"))
      (node (ref "C28") (pin "2") (pinfunction "2_2") (pintype "passive"))
      (node (ref "C29") (pin "2") (pinfunction "2_2") (pintype "passive"))
      (node (ref "C3") (pin "2") (pinfunction "2_2") (pintype "passive"))
      (node (ref "C30") (pin "2") (pinfunction "2_2") (pintype "passive"))
      (node (ref "C31") (pin "2") (pinfunction "2_2") (pintype "passive"))
      (node (ref "C32") (pin "2") (pinfunction "2_2") (pintype "passive"))
      (node (ref "C34") (pin "2") (pinfunction "2_2") (pintype "passive"))
      (node (ref "C35") (pin "2") (pinfunction "2_2") (pintype "passive"))
      (node (ref "C36") (pin "2") (pinfunction "2_2") (pintype "passive"))
      (node (ref "C37") (pin "2") (pinfunction "2_2") (pintype "passive"))
      (node (ref "C38") (pin "2") (pinfunction "2_2") (pintype "passive"))
      (node (ref "C39") (pin "2") (pinfunction "2_2") (pintype "passive"))
      (node (ref "C4") (pin "2") (pinfunction "2_2") (pintype "passive"))
      (node (ref "C40") (pin "2") (pinfunction "2_2") (pintype "passive"))
      (node (ref "C41") (pin "2") (pinfunction "2_2") (pintype "passive"))
      (node (ref "C42") (pin "2") (pinfunction "2_2") (pintype "passive"))
      (node (ref "C43") (pin "2") (pinfunction "2_2") (pintype "passive"))
      (node (ref "C44") (pin "-") (pinfunction "-_-") (pintype "passive"))
      (node (ref "C45") (pin "-") (pinfunction "-_-") (pintype "passive"))
      (node (ref "C46") (pin "2") (pinfunction "2_2") (pintype "passive"))
      (node (ref "C47") (pin "2") (pinfunction "2_2") (pintype "passive"))
      (node (ref "C48") (pin "2") (pinfunction "2_2") (pintype "passive"))
      (node (ref "C49") (pin "2") (pinfunction "2_2") (pintype "passive"))
      (node (ref "C5") (pin "2") (pinfunction "2_2") (pintype "passive"))
      (node (ref "C52") (pin "2") (pinfunction "2_2") (pintype "passive"))
      (node (ref "C6") (pin "2") (pinfunction "2_2") (pintype "passive"))
      (node (ref "C7") (pin "2") (pinfunction "2_2") (pintype "passive"))
      (node (ref "C8") (pin "2") (pinfunction "2_2") (pintype "passive"))
      (node (ref "C9") (pin "2") (pinfunction "2_2") (pintype "passive"))
      (node (ref "DVD") (pin "2") (pinfunction "2_2") (pintype "passive"))
      (node (ref "DVD") (pin "39") (pinfunction "39_39") (pintype "passive"))
      (node (ref "DVD") (pin "6") (pinfunction "6_6") (pintype "passive"))
      (node (ref "FBK") (pin "GND") (pinfunction "GND_GND") (pintype "bidirectional"))
      (node (ref "FOC") (pin "1") (pinfunction "PPAD_1") (pintype "bidirectional"))
      (node (ref "FOC") (pin "10") (pinfunction "PPAD_10") (pintype "bidirectional"))
      (node (ref "FOC") (pin "11") (pinfunction "PPAD_11") (pintype "bidirectional"))
      (node (ref "FOC") (pin "17") (pinfunction "V-_17") (pintype "bidirectional"))
      (node (ref "FOC") (pin "18") (pinfunction "V-_18") (pintype "bidirectional"))
      (node (ref "FOC") (pin "20") (pinfunction "PPAD_20") (pintype "bidirectional"))
      (node (ref "FOC") (pin "TH") (pinfunction "PPADHS_TH") (pintype "bidirectional"))
      (node (ref "H/L") (pin "3") (pinfunction "3_3") (pintype "passive"))
      (node (ref "IC1") (pin "23") (pinfunction "VSS_2_23") (pintype "power_in"))
      (node (ref "IC1") (pin "35") (pinfunction "VSS_3_35") (pintype "power_in"))
      (node (ref "IC1") (pin "47") (pinfunction "VSS_1_47") (pintype "power_in"))
      (node (ref "IC1") (pin "8") (pinfunction "VSSA_8") (pintype "power_in"))
      (node (ref "IC10") (pin "2") (pinfunction "V-_2") (pintype "power_in"))
      (node (ref "IC2") (pin "2") (pinfunction "GND_2") (pintype "power_in"))
      (node (ref "IC3") (pin "2") (pinfunction "GND_2") (pintype "power_in"))
      (node (ref "IC4") (pin "3") (pinfunction "GND_3") (pintype "passive"))
      (node (ref "IC5") (pin "2") (pinfunction "GND_2") (pintype "power_in"))
      (node (ref "IC6") (pin "2") (pinfunction "GND_2") (pintype "power_in"))
      (node (ref "IC7") (pin "2") (pinfunction "GND_2") (pintype "power_in"))
      (node (ref "IC9") (pin "1") (pinfunction "GND_1") (pintype "bidirectional"))
      (node (ref "L-") (pin "1") (pinfunction "1_1") (pintype "passive"))
      (node (ref "POWER") (pin "2") (pinfunction "2_2") (pintype "passive"))
      (node (ref "PWM") (pin "3") (pinfunction "3_3") (pintype "passive"))
      (node (ref "R/W") (pin "3") (pinfunction "3_3") (pintype "passive"))
      (node (ref "R16") (pin "2") (pinfunction "2_2") (pintype "passive"))
      (node (ref "R17") (pin "2") (pinfunction "2_2") (pintype "passive"))
      (node (ref "R18") (pin "2") (pinfunction "2_2") (pintype "passive"))
      (node (ref "R19") (pin "2") (pinfunction "2_2") (pintype "passive"))
      (node (ref "R21") (pin "2") (pinfunction "2_2") (pintype "passive"))
      (node (ref "R22") (pin "2") (pinfunction "2_2") (pintype "passive"))
      (node (ref "R26") (pin "2") (pinfunction "2_2") (pintype "passive"))
      (node (ref "R27") (pin "2") (pinfunction "2_2") (pintype "passive"))
      (node (ref "R28") (pin "2") (pinfunction "2_2") (pintype "passive"))
      (node (ref "R33") (pin "2") (pinfunction "2_2") (pintype "passive"))
      (node (ref "R35") (pin "2") (pinfunction "2_2") (pintype "passive"))
      (node (ref "R36") (pin "2") (pinfunction "2_2") (pintype "passive"))
      (node (ref "R39") (pin "2") (pinfunction "2_2") (pintype "passive"))
      (node (ref "R40") (pin "2") (pinfunction "2_2") (pintype "passive"))
      (node (ref "R41") (pin "2") (pinfunction "2_2") (pintype "passive"))
      (node (ref "R42") (pin "2") (pinfunction "2_2") (pintype "passive"))
      (node (ref "R43") (pin "2") (pinfunction "2_2") (pintype "passive"))
      (node (ref "R44") (pin "2") (pinfunction "2_2") (pintype "passive"))
      (node (ref "R47") (pin "2") (pinfunction "2_2") (pintype "passive"))
      (node (ref "R48") (pin "2") (pinfunction "2_2") (pintype "passive"))
      (node (ref "R49") (pin "2") (pinfunction "2_2") (pintype "passive"))
      (node (ref "RAD") (pin "1") (pinfunction "PPAD_1") (pintype "bidirectional"))
      (node (ref "RAD") (pin "10") (pinfunction "PPAD_10") (pintype "bidirectional"))
      (node (ref "RAD") (pin "11") (pinfunction "PPAD_11") (pintype "bidirectional"))
      (node (ref "RAD") (pin "17") (pinfunction "V-_17") (pintype "bidirectional"))
      (node (ref "RAD") (pin "18") (pinfunction "V-_18") (pintype "bidirectional"))
      (node (ref "RAD") (pin "20") (pinfunction "PPAD_20") (pintype "bidirectional"))
      (node (ref "RAD") (pin "TH") (pinfunction "PPADHS_TH") (pintype "bidirectional"))
      (node (ref "SPEED") (pin "3") (pinfunction "3_3") (pintype "passive"))
      (node (ref "SWD") (pin "3") (pinfunction "3_3") (pintype "passive"))
      (node (ref "TRG") (pin "2") (pinfunction "2_2") (pintype "passive"))
      (node (ref "U$3") (pin "1") (pinfunction "1_1") (pintype "passive"))
      (node (ref "U$9") (pin "1") (pinfunction "1_1") (pintype "passive"))
      (node (ref "U1") (pin "4") (pinfunction "V-_4") (pintype "power_in"))
      (node (ref "U2") (pin "4") (pinfunction "V-_4") (pintype "power_in"))
      (node (ref "U3") (pin "6") (pinfunction "DGND_6") (pintype "power_in"))
      (node (ref "U3") (pin "7") (pinfunction "AGND_7") (pintype "power_in"))
      (node (ref "U3") (pin "8") (pinfunction "~{LDAC}_8") (pintype "input"))
      (node (ref "U4") (pin "4") (pinfunction "V-_4") (pintype "power_in"))
      (node (ref "USART") (pin "4") (pinfunction "4_4") (pintype "passive"))
      (node (ref "USB") (pin "5") (pinfunction "5_5") (pintype "passive"))
      (node (ref "USB") (pin "M1") (pinfunction "S1_M1") (pintype "passive"))
      (node (ref "USB") (pin "M2") (pinfunction "S2_M2") (pintype "passive"))
      (node (ref "USB") (pin "M3") (pinfunction "S3_M3") (pintype "passive"))
      (node (ref "USB") (pin "M4") (pinfunction "S4_M4") (pintype "passive"))
      (node (ref "V-") (pin "1") (pinfunction "1_1") (pintype "passive"))
      (node (ref "X1") (pin "2") (pinfunction "2_2") (pintype "passive"))
      (node (ref "X1") (pin "4") (pinfunction "4_4") (pintype "passive"))
    )
    (net (code "53") (name "Net-(A-PadC)") (class "Default")
      (node (ref "A") (pin "C") (pinfunction "C_C") (pintype "passive"))
      (node (ref "R49") (pin "1") (pinfunction "1_1") (pintype "passive"))
    )
    (net (code "54") (name "Net-(B-PadC)") (class "Default")
      (node (ref "B") (pin "C") (pinfunction "C_C") (pintype "passive"))
      (node (ref "R47") (pin "1") (pinfunction "1_1") (pintype "passive"))
    )
    (net (code "55") (name "Net-(D6-PadC)") (class "Default")
      (node (ref "D6") (pin "C") (pinfunction "C_C") (pintype "passive"))
      (node (ref "R41") (pin "1") (pinfunction "1_1") (pintype "passive"))
    )
    (net (code "56") (name "Net-(D7-PadC)") (class "Default")
      (node (ref "D7") (pin "C") (pinfunction "C_C") (pintype "passive"))
      (node (ref "R43") (pin "1") (pinfunction "1_1") (pintype "passive"))
    )
    (net (code "57") (name "Net-(DVD-Pad3)") (class "Default")
      (node (ref "DVD") (pin "3") (pinfunction "3_3") (pintype "passive"))
      (node (ref "R20") (pin "1") (pinfunction "1_1") (pintype "passive"))
    )
    (net (code "58") (name "Net-(DVD-Pad4)") (class "Default")
      (node (ref "DVD") (pin "4") (pinfunction "4_4") (pintype "passive"))
      (node (ref "R20") (pin "2") (pinfunction "2_2") (pintype "passive"))
    )
    (net (code "59") (name "Net-(FOC-CLSET)") (class "Default")
      (node (ref "FOC") (pin "3") (pinfunction "CLSET_3") (pintype "bidirectional"))
      (node (ref "R21") (pin "1") (pinfunction "1_1") (pintype "passive"))
    )
    (net (code "60") (name "Net-(FOC-EN)") (class "Default")
      (node (ref "FOC") (pin "7") (pinfunction "THFLAG_7") (pintype "bidirectional"))
      (node (ref "FOC") (pin "8") (pinfunction "EN_8") (pintype "bidirectional"))
    )
    (net (code "61") (name "Net-(FOC-IN+)") (class "Default")
      (node (ref "FOC") (pin "6") (pinfunction "IN+_6") (pintype "bidirectional"))
      (node (ref "R24") (pin "1") (pinfunction "1_1") (pintype "passive"))
      (node (ref "R26") (pin "1") (pinfunction "1_1") (pintype "passive"))
    )
    (net (code "62") (name "Net-(IC2-NR)") (class "Default")
      (node (ref "C11") (pin "1") (pinfunction "1_1") (pintype "passive"))
      (node (ref "IC2") (pin "4") (pinfunction "NR_4") (pintype "passive"))
    )
    (net (code "63") (name "Net-(IC3-EN)") (class "Default")
      (node (ref "C17") (pin "1") (pinfunction "1_1") (pintype "passive"))
      (node (ref "IC3") (pin "1") (pinfunction "IN_1") (pintype "power_in"))
      (node (ref "IC3") (pin "3") (pinfunction "EN_3") (pintype "passive"))
      (node (ref "L3") (pin "2") (pinfunction "2_2") (pintype "passive"))
    )
    (net (code "64") (name "Net-(IC3-NR)") (class "Default")
      (node (ref "C10") (pin "1") (pinfunction "1_1") (pintype "passive"))
      (node (ref "IC3") (pin "4") (pinfunction "NR_4") (pintype "passive"))
    )
    (net (code "65") (name "Net-(IC5-IN)") (class "Default")
      (node (ref "C30") (pin "1") (pinfunction "1_1") (pintype "passive"))
      (node (ref "IC5") (pin "1") (pinfunction "IN_1") (pintype "power_in"))
      (node (ref "IC5") (pin "3") (pinfunction "ON_3") (pintype "passive"))
      (node (ref "L2") (pin "2") (pinfunction "2_2") (pintype "passive"))
    )
    (net (code "66") (name "Net-(IC7-FB)") (class "Default")
      (node (ref "C33") (pin "2") (pinfunction "2_2") (pintype "passive"))
      (node (ref "IC7") (pin "3") (pinfunction "FB_3") (pintype "input"))
      (node (ref "R28") (pin "1") (pinfunction "1_1") (pintype "passive"))
      (node (ref "R30") (pin "2") (pinfunction "2_2") (pintype "passive"))
    )
    (net (code "67") (name "Net-(IC7-OVP)") (class "Default")
      (node (ref "IC7") (pin "5") (pinfunction "OVP_5") (pintype "input"))
      (node (ref "R27") (pin "1") (pinfunction "1_1") (pintype "passive"))
      (node (ref "R29") (pin "2") (pinfunction "2_2") (pintype "passive"))
    )
    (net (code "68") (name "Net-(IC7-SW)") (class "Default")
      (node (ref "D5") (pin "A") (pinfunction "A_A") (pintype "passive"))
      (node (ref "IC7") (pin "1") (pinfunction "SW_1") (pintype "input"))
      (node (ref "L4") (pin "2") (pinfunction "2_2") (pintype "passive"))
    )
    (net (code "69") (name "Net-(IC8-OUT)") (class "Default")
      (node (ref "IC8") (pin "2") (pinfunction "OUT_2") (pintype "passive"))
      (node (ref "R45") (pin "1") (pinfunction "1_1") (pintype "passive"))
    )
    (net (code "70") (name "Net-(IC9-AGND)") (class "Default")
      (node (ref "C50") (pin "2") (pinfunction "2_2") (pintype "passive"))
      (node (ref "IC9") (pin "3") (pinfunction "AGND_3") (pintype "bidirectional"))
      (node (ref "P1") (pin "2") (pinfunction "S_2") (pintype "passive"))
      (node (ref "P1") (pin "3") (pinfunction "E_3") (pintype "passive"))
    )
    (net (code "71") (name "Net-(IC9-CI)") (class "Default")
      (node (ref "C50") (pin "1") (pinfunction "1_1") (pintype "passive"))
      (node (ref "IC9") (pin "2") (pinfunction "CI_2") (pintype "bidirectional"))
    )
    (net (code "72") (name "Net-(IC9-MDA)") (class "Default")
      (node (ref "IC9") (pin "5") (pinfunction "MDA_5") (pintype "bidirectional"))
      (node (ref "R50") (pin "2") (pinfunction "2_2") (pintype "passive"))
    )
    (net (code "73") (name "Net-(IC10--IN)") (class "Default")
      (node (ref "IC10") (pin "4") (pinfunction "-IN_4") (pintype "input"))
      (node (ref "R51") (pin "1") (pinfunction "1_1") (pintype "passive"))
    )
    (net (code "74") (name "Net-(IC10-OUT)") (class "Default")
      (node (ref "IC10") (pin "1") (pinfunction "OUT_1") (pintype "output"))
      (node (ref "R51") (pin "2") (pinfunction "2_2") (pintype "passive"))
      (node (ref "R52") (pin "1") (pinfunction "1_1") (pintype "passive"))
    )
    (net (code "75") (name "Net-(L1-Pad2)") (class "Default")
      (node (ref "L1") (pin "2") (pinfunction "2_2") (pintype "passive"))
      (node (ref "USB") (pin "1") (pinfunction "1_1") (pintype "passive"))
    )
    (net (code "76") (name "Net-(P1-A)") (class "Default")
      (node (ref "P1") (pin "1") (pinfunction "A_1") (pintype "passive"))
      (node (ref "R50") (pin "1") (pinfunction "1_1") (pintype "passive"))
    )
    (net (code "77") (name "Net-(PWR-PadC)") (class "Default")
      (node (ref "PWR") (pin "C") (pinfunction "C_C") (pintype "passive"))
      (node (ref "R48") (pin "1") (pinfunction "1_1") (pintype "passive"))
    )
    (net (code "78") (name "Net-(R1-Pad2)") (class "Default")
      (node (ref "R1") (pin "2") (pinfunction "2_2") (pintype "passive"))
      (node (ref "USB") (pin "2") (pinfunction "2_2") (pintype "passive"))
    )
    (net (code "79") (name "Net-(R2-Pad2)") (class "Default")
      (node (ref "R2") (pin "2") (pinfunction "2_2") (pintype "passive"))
      (node (ref "USB") (pin "3") (pinfunction "3_3") (pintype "passive"))
    )
    (net (code "80") (name "Net-(R29-Pad1)") (class "Default")
      (node (ref "R29") (pin "1") (pinfunction "1_1") (pintype "passive"))
      (node (ref "R31") (pin "2") (pinfunction "2_2") (pintype "passive"))
    )
    (net (code "81") (name "Net-(R45-Pad2)") (class "Default")
      (node (ref "R45") (pin "2") (pinfunction "2_2") (pintype "passive"))
      (node (ref "R46") (pin "1") (pinfunction "1_1") (pintype "passive"))
      (node (ref "R46") (pin "3") (pinfunction "3_3") (pintype "passive"))
    )
    (net (code "82") (name "Net-(RAD-CLSET)") (class "Default")
      (node (ref "R22") (pin "1") (pinfunction "1_1") (pintype "passive"))
      (node (ref "RAD") (pin "3") (pinfunction "CLSET_3") (pintype "bidirectional"))
    )
    (net (code "83") (name "Net-(RAD-EN)") (class "Default")
      (node (ref "RAD") (pin "7") (pinfunction "THFLAG_7") (pintype "bidirectional"))
      (node (ref "RAD") (pin "8") (pinfunction "EN_8") (pintype "bidirectional"))
    )
    (net (code "84") (name "Net-(RAD-IN+)") (class "Default")
      (node (ref "R25") (pin "1") (pinfunction "1_1") (pintype "passive"))
      (node (ref "RAD") (pin "6") (pinfunction "IN+_6") (pintype "bidirectional"))
    )
    (net (code "85") (name "Net-(U1A-+IN)") (class "Default")
      (node (ref "R17") (pin "1") (pinfunction "1_1") (pintype "passive"))
      (node (ref "R9") (pin "1") (pinfunction "1_1") (pintype "passive"))
      (node (ref "U1") (pin "3") (pinfunction "+IN_3") (pintype "input"))
    )
    (net (code "86") (name "Net-(U1A--IN)") (class "Default")
      (node (ref "R5") (pin "1") (pinfunction "1_1") (pintype "passive"))
      (node (ref "U1") (pin "2") (pinfunction "-IN_2") (pintype "input"))
    )
    (net (code "87") (name "Net-(U1A-OUT)") (class "Default")
      (node (ref "R13") (pin "1") (pinfunction "1_1") (pintype "passive"))
      (node (ref "R5") (pin "2") (pinfunction "2_2") (pintype "passive"))
      (node (ref "U1") (pin "1") (pinfunction "OUT_1") (pintype "output"))
    )
    (net (code "88") (name "Net-(U1B-+IN)") (class "Default")
      (node (ref "R16") (pin "1") (pinfunction "1_1") (pintype "passive"))
      (node (ref "R8") (pin "1") (pinfunction "1_1") (pintype "passive"))
      (node (ref "U1") (pin "5") (pinfunction "+IN_5") (pintype "input"))
    )
    (net (code "89") (name "Net-(U1B--IN)") (class "Default")
      (node (ref "R4") (pin "1") (pinfunction "1_1") (pintype "passive"))
      (node (ref "U1") (pin "6") (pinfunction "-IN_6") (pintype "input"))
    )
    (net (code "90") (name "Net-(U1B-OUT)") (class "Default")
      (node (ref "R12") (pin "1") (pinfunction "1_1") (pintype "passive"))
      (node (ref "R4") (pin "2") (pinfunction "2_2") (pintype "passive"))
      (node (ref "U1") (pin "7") (pinfunction "OUT_7") (pintype "output"))
    )
    (net (code "91") (name "Net-(U2A-+IN)") (class "Default")
      (node (ref "R11") (pin "1") (pinfunction "1_1") (pintype "passive"))
      (node (ref "R19") (pin "1") (pinfunction "1_1") (pintype "passive"))
      (node (ref "U2") (pin "3") (pinfunction "+IN_3") (pintype "input"))
    )
    (net (code "92") (name "Net-(U2A--IN)") (class "Default")
      (node (ref "R7") (pin "1") (pinfunction "1_1") (pintype "passive"))
      (node (ref "U2") (pin "2") (pinfunction "-IN_2") (pintype "input"))
    )
    (net (code "93") (name "Net-(U2A-OUT)") (class "Default")
      (node (ref "R15") (pin "1") (pinfunction "1_1") (pintype "passive"))
      (node (ref "R7") (pin "2") (pinfunction "2_2") (pintype "passive"))
      (node (ref "U2") (pin "1") (pinfunction "OUT_1") (pintype "output"))
    )
    (net (code "94") (name "Net-(U2B-+IN)") (class "Default")
      (node (ref "R10") (pin "1") (pinfunction "1_1") (pintype "passive"))
      (node (ref "R18") (pin "1") (pinfunction "1_1") (pintype "passive"))
      (node (ref "U2") (pin "5") (pinfunction "+IN_5") (pintype "input"))
    )
    (net (code "95") (name "Net-(U2B--IN)") (class "Default")
      (node (ref "R6") (pin "1") (pinfunction "1_1") (pintype "passive"))
      (node (ref "U2") (pin "6") (pinfunction "-IN_6") (pintype "input"))
    )
    (net (code "96") (name "Net-(U2B-OUT)") (class "Default")
      (node (ref "R14") (pin "1") (pinfunction "1_1") (pintype "passive"))
      (node (ref "R6") (pin "2") (pinfunction "2_2") (pintype "passive"))
      (node (ref "U2") (pin "7") (pinfunction "OUT_7") (pintype "output"))
    )
    (net (code "97") (name "Net-(U4A-+IN)") (class "Default")
      (node (ref "R37") (pin "1") (pinfunction "1_1") (pintype "passive"))
      (node (ref "R39") (pin "1") (pinfunction "1_1") (pintype "passive"))
      (node (ref "U4") (pin "3") (pinfunction "+IN_3") (pintype "input"))
    )
    (net (code "98") (name "Net-(U4B-+IN)") (class "Default")
      (node (ref "R38") (pin "1") (pinfunction "1_1") (pintype "passive"))
      (node (ref "R40") (pin "1") (pinfunction "1_1") (pintype "passive"))
      (node (ref "U4") (pin "5") (pinfunction "+IN_5") (pintype "input"))
    )
    (net (code "99") (name "VCC") (class "Default")
      (node (ref "7V5") (pin "1") (pinfunction "1_1") (pintype "passive"))
      (node (ref "C27") (pin "+") (pinfunction "+_+") (pintype "passive"))
      (node (ref "C28") (pin "1") (pinfunction "1_1") (pintype "passive"))
      (node (ref "C44") (pin "+") (pinfunction "+_+") (pintype "passive"))
      (node (ref "C46") (pin "1") (pinfunction "1_1") (pintype "passive"))
      (node (ref "IC4") (pin "1") (pinfunction "VI_1") (pintype "input"))
      (node (ref "IC8") (pin "3") (pinfunction "IN_3") (pintype "input"))
      (node (ref "L2") (pin "1") (pinfunction "1_1") (pintype "passive"))
      (node (ref "POWER") (pin "1") (pinfunction "1_1") (pintype "passive"))
    )
    (net (code "100") (name "unconnected-(7V5-Pad2)") (class "Default")
      (node (ref "7V5") (pin "2") (pinfunction "2_2") (pintype "passive"))
    )
    (net (code "101") (name "unconnected-(DVD-Pad7)") (class "Default")
      (node (ref "DVD") (pin "7") (pinfunction "7_7") (pintype "passive"))
    )
    (net (code "102") (name "unconnected-(DVD-Pad8)") (class "Default")
      (node (ref "DVD") (pin "8") (pinfunction "8_8") (pintype "passive"))
    )
    (net (code "103") (name "unconnected-(DVD-Pad9)") (class "Default")
      (node (ref "DVD") (pin "9") (pinfunction "9_9") (pintype "passive"))
    )
    (net (code "104") (name "unconnected-(DVD-Pad10)") (class "Default")
      (node (ref "DVD") (pin "10") (pinfunction "10_10") (pintype "passive"))
    )
    (net (code "105") (name "unconnected-(DVD-Pad11)") (class "Default")
      (node (ref "DVD") (pin "11") (pinfunction "11_11") (pintype "passive"))
    )
    (net (code "106") (name "unconnected-(DVD-Pad12)") (class "Default")
      (node (ref "DVD") (pin "12") (pinfunction "12_12") (pintype "passive"))
    )
    (net (code "107") (name "unconnected-(DVD-Pad13)") (class "Default")
      (node (ref "DVD") (pin "13") (pinfunction "13_13") (pintype "passive"))
    )
    (net (code "108") (name "unconnected-(DVD-Pad14)") (class "Default")
      (node (ref "DVD") (pin "14") (pinfunction "14_14") (pintype "passive"))
    )
    (net (code "109") (name "unconnected-(DVD-Pad15)") (class "Default")
      (node (ref "DVD") (pin "15") (pinfunction "15_15") (pintype "passive"))
    )
    (net (code "110") (name "unconnected-(DVD-Pad16)") (class "Default")
      (node (ref "DVD") (pin "16") (pinfunction "16_16") (pintype "passive"))
    )
    (net (code "111") (name "unconnected-(DVD-Pad17)") (class "Default")
      (node (ref "DVD") (pin "17") (pinfunction "17_17") (pintype "passive"))
    )
    (net (code "112") (name "unconnected-(DVD-Pad18)") (class "Default")
      (node (ref "DVD") (pin "18") (pinfunction "18_18") (pintype "passive"))
    )
    (net (code "113") (name "unconnected-(DVD-Pad19)") (class "Default")
      (node (ref "DVD") (pin "19") (pinfunction "19_19") (pintype "passive"))
    )
    (net (code "114") (name "unconnected-(DVD-Pad20)") (class "Default")
      (node (ref "DVD") (pin "20") (pinfunction "20_20") (pintype "passive"))
    )
    (net (code "115") (name "unconnected-(DVD-Pad21)") (class "Default")
      (node (ref "DVD") (pin "21") (pinfunction "21_21") (pintype "passive"))
    )
    (net (code "116") (name "unconnected-(DVD-Pad22)") (class "Default")
      (node (ref "DVD") (pin "22") (pinfunction "22_22") (pintype "passive"))
    )
    (net (code "117") (name "unconnected-(DVD-Pad23)") (class "Default")
      (node (ref "DVD") (pin "23") (pinfunction "23_23") (pintype "passive"))
    )
    (net (code "118") (name "unconnected-(DVD-Pad24)") (class "Default")
      (node (ref "DVD") (pin "24") (pinfunction "24_24") (pintype "passive"))
    )
    (net (code "119") (name "unconnected-(DVD-Pad25)") (class "Default")
      (node (ref "DVD") (pin "25") (pinfunction "25_25") (pintype "passive"))
    )
    (net (code "120") (name "unconnected-(DVD-Pad26)") (class "Default")
      (node (ref "DVD") (pin "26") (pinfunction "26_26") (pintype "passive"))
    )
    (net (code "121") (name "unconnected-(DVD-Pad27)") (class "Default")
      (node (ref "DVD") (pin "27") (pinfunction "27_27") (pintype "passive"))
    )
    (net (code "122") (name "unconnected-(DVD-Pad28)") (class "Default")
      (node (ref "DVD") (pin "28") (pinfunction "28_28") (pintype "passive"))
    )
    (net (code "123") (name "unconnected-(DVD-Pad29)") (class "Default")
      (node (ref "DVD") (pin "29") (pinfunction "29_29") (pintype "passive"))
    )
    (net (code "124") (name "unconnected-(DVD-Pad31)") (class "Default")
      (node (ref "DVD") (pin "31") (pinfunction "31_31") (pintype "passive"))
    )
    (net (code "125") (name "unconnected-(DVD-Pad32)") (class "Default")
      (node (ref "DVD") (pin "32") (pinfunction "32_32") (pintype "passive"))
    )
    (net (code "126") (name "unconnected-(DVD-Pad37)") (class "Default")
      (node (ref "DVD") (pin "37") (pinfunction "37_37") (pintype "passive"))
    )
    (net (code "127") (name "unconnected-(DVD-Pad38)") (class "Default")
      (node (ref "DVD") (pin "38") (pinfunction "38_38") (pintype "passive"))
    )
    (net (code "128") (name "unconnected-(DVD-Pad43)") (class "Default")
      (node (ref "DVD") (pin "43") (pinfunction "43_43") (pintype "passive"))
    )
    (net (code "129") (name "unconnected-(DVD-Pad44)") (class "Default")
      (node (ref "DVD") (pin "44") (pinfunction "44_44") (pintype "passive"))
    )
    (net (code "130") (name "unconnected-(FOC-CLFLAG-Pad4)") (class "Default")
      (node (ref "FOC") (pin "4") (pinfunction "CLFLAG_4") (pintype "bidirectional"))
    )
    (net (code "131") (name "unconnected-(FOC-IMON-Pad19)") (class "Default")
      (node (ref "FOC") (pin "19") (pinfunction "IMON_19") (pintype "bidirectional"))
    )
    (net (code "132") (name "unconnected-(FOC-POUT1-Pad2)") (class "Default")
      (node (ref "FOC") (pin "2") (pinfunction "POUT1_2") (pintype "bidirectional"))
    )
    (net (code "133") (name "unconnected-(FOC-POUT2-Pad9)") (class "Default")
      (node (ref "FOC") (pin "9") (pinfunction "POUT2_9") (pintype "bidirectional"))
    )
    (net (code "134") (name "unconnected-(IC1B-PA8-Pad29)") (class "Default")
      (node (ref "IC1") (pin "29") (pinfunction "PA8_29") (pintype "bidirectional"))
    )
    (net (code "135") (name "unconnected-(IC1C-PA1{slash}ADC1_CH2-Pad11)") (class "Default")
      (node (ref "IC1") (pin "11") (pinfunction "PA1/ADC1_CH2_11") (pintype "bidirectional"))
    )
    (net (code "136") (name "unconnected-(IC1C-PA2{slash}ADC1_CH3-Pad12)") (class "Default")
      (node (ref "IC1") (pin "12") (pinfunction "PA2/ADC1_CH3_12") (pintype "bidirectional"))
    )
    (net (code "137") (name "unconnected-(IC1C-PA3{slash}ADC1_CH4-Pad13)") (class "Default")
      (node (ref "IC1") (pin "13") (pinfunction "PA3/ADC1_CH4_13") (pintype "bidirectional"))
    )
    (net (code "138") (name "unconnected-(IC1C-PA7{slash}ADC2_CH4-Pad17)") (class "Default")
      (node (ref "IC1") (pin "17") (pinfunction "PA7/ADC2_CH4_17") (pintype "bidirectional"))
    )
    (net (code "139") (name "unconnected-(IC1D-PB12-Pad25)") (class "Default")
      (node (ref "IC1") (pin "25") (pinfunction "PB12_25") (pintype "bidirectional"))
    )
    (net (code "140") (name "unconnected-(IC1D-PB15-Pad28)") (class "Default")
      (node (ref "IC1") (pin "28") (pinfunction "PB15_28") (pintype "bidirectional"))
    )
    (net (code "141") (name "unconnected-(IC1D-TIM2_CH3{slash}PB10-Pad21)") (class "Default")
      (node (ref "IC1") (pin "21") (pinfunction "TIM2_CH3/PB10_21") (pintype "bidirectional"))
    )
    (net (code "142") (name "unconnected-(IC1D-TIM2_CH4{slash}PB11-Pad22)") (class "Default")
      (node (ref "IC1") (pin "22") (pinfunction "TIM2_CH4/PB11_22") (pintype "bidirectional"))
    )
    (net (code "143") (name "unconnected-(IC1D-TIM4_CH3{slash}PB8-Pad45)") (class "Default")
      (node (ref "IC1") (pin "45") (pinfunction "TIM4_CH3/PB8_45") (pintype "bidirectional"))
    )
    (net (code "144") (name "unconnected-(IC1E-PB2-Pad20)") (class "Default")
      (node (ref "IC1") (pin "20") (pinfunction "PB2_20") (pintype "bidirectional"))
    )
    (net (code "145") (name "unconnected-(IC1E-PB7-Pad43)") (class "Default")
      (node (ref "IC1") (pin "43") (pinfunction "PB7_43") (pintype "bidirectional"))
    )
    (net (code "146") (name "unconnected-(IC1F-PC13-Pad2)") (class "Default")
      (node (ref "IC1") (pin "2") (pinfunction "PC13_2") (pintype "bidirectional"))
    )
    (net (code "147") (name "unconnected-(IC1F-PC14-Pad3)") (class "Default")
      (node (ref "IC1") (pin "3") (pinfunction "PC14_3") (pintype "bidirectional"))
    )
    (net (code "148") (name "unconnected-(IC1F-PC15-Pad4)") (class "Default")
      (node (ref "IC1") (pin "4") (pinfunction "PC15_4") (pintype "bidirectional"))
    )
    (net (code "149") (name "unconnected-(RAD-CLFLAG-Pad4)") (class "Default")
      (node (ref "RAD") (pin "4") (pinfunction "CLFLAG_4") (pintype "bidirectional"))
    )
    (net (code "150") (name "unconnected-(RAD-IMON-Pad19)") (class "Default")
      (node (ref "RAD") (pin "19") (pinfunction "IMON_19") (pintype "bidirectional"))
    )
    (net (code "151") (name "unconnected-(RAD-POUT1-Pad2)") (class "Default")
      (node (ref "RAD") (pin "2") (pinfunction "POUT1_2") (pintype "bidirectional"))
    )
    (net (code "152") (name "unconnected-(RAD-POUT2-Pad9)") (class "Default")
      (node (ref "RAD") (pin "9") (pinfunction "POUT2_9") (pintype "bidirectional"))
    )
    (net (code "153") (name "unconnected-(U3-VOUTB-Pad11)") (class "Default")
      (node (ref "U3") (pin "11") (pinfunction "VOUTB_11") (pintype "output"))
    )
    (net (code "154") (name "unconnected-(U3-VOUTC-Pad10)") (class "Default")
      (node (ref "U3") (pin "10") (pinfunction "VOUTC_10") (pintype "output"))
    )
    (net (code "155") (name "unconnected-(U3-VOUTD-Pad9)") (class "Default")
      (node (ref "U3") (pin "9") (pinfunction "VOUTD_9") (pintype "output"))
    )
    (net (code "156") (name "unconnected-(U3-~{ALARM}-Pad15)") (class "Default")
      (node (ref "U3") (pin "15") (pinfunction "~{ALARM}_15") (pintype "output"))
    )
    (net (code "157") (name "unconnected-(USB-Pad4)") (class "Default")
      (node (ref "USB") (pin "4") (pinfunction "4_4") (pintype "passive"))
    )
  )
)
